# main.net
KiCad netlist of a schematic drawn in Altium Designer
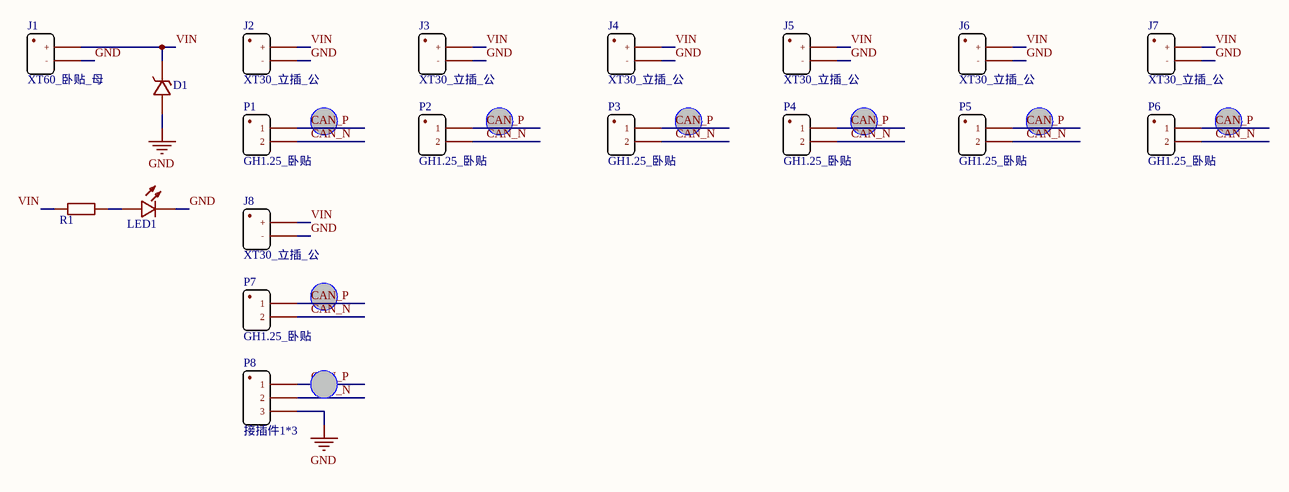
[diagram p0: main.SchDoc]

(export (version "E")
  (design (tool "Eeschema 10.0.6"))
  (components
    (comp (ref "D1") (value "SMAJ24A") (footprint "SMA") (libsource (lib "元件库") (part "二极管_瞬态抑制")))
    (comp (ref "J1") (value "XT60_卧贴_母") (footprint "XT60-PT-M") (libsource (lib "接口库") (part "接口_XT")))
    (comp (ref "J2") (value "XT30_立插_公") (footprint "XT30-UPB-F") (libsource (lib "接口库") (part "接口_XT")))
    (comp (ref "J3") (value "XT30_立插_公") (footprint "XT30-UPB-F") (libsource (lib "接口库") (part "接口_XT")))
    (comp (ref "J4") (value "XT30_立插_公") (footprint "XT30-UPB-F") (libsource (lib "接口库") (part "接口_XT")))
    (comp (ref "J5") (value "XT30_立插_公") (footprint "XT30-UPB-F") (libsource (lib "接口库") (part "接口_XT")))
    (comp (ref "J6") (value "XT30_立插_公") (footprint "XT30-UPB-F") (libsource (lib "接口库") (part "接口_XT")))
    (comp (ref "J7") (value "XT30_立插_公") (footprint "XT30-UPB-F") (libsource (lib "接口库") (part "接口_XT")))
    (comp (ref "J8") (value "XT30_立插_公") (footprint "XT30-UPB-F") (libsource (lib "接口库") (part "接口_XT")))
    (comp (ref "LED1") (value "LED") (footprint "0603D") (libsource (lib "元件库") (part "二极管_贴片发光")))
    (comp (ref "P1") (value "GH1.25_卧贴") (footprint "GH1.25-PW-1*2") (libsource (lib "接口库") (part "接插件1*2")))
    (comp (ref "P2") (value "GH1.25_卧贴") (footprint "GH1.25-PW-1*2") (libsource (lib "接口库") (part "接插件1*2")))
    (comp (ref "P3") (value "GH1.25_卧贴") (footprint "GH1.25-PW-1*2") (libsource (lib "接口库") (part "接插件1*2")))
    (comp (ref "P4") (value "GH1.25_卧贴") (footprint "GH1.25-PW-1*2") (libsource (lib "接口库") (part "接插件1*2")))
    (comp (ref "P5") (value "GH1.25_卧贴") (footprint "GH1.25-PW-1*2") (libsource (lib "接口库") (part "接插件1*2")))
    (comp (ref "P6") (value "GH1.25_卧贴") (footprint "GH1.25-PW-1*2") (libsource (lib "接口库") (part "接插件1*2")))
    (comp (ref "P7") (value "GH1.25_卧贴") (footprint "GH1.25-PW-1*2") (libsource (lib "接口库") (part "接插件1*2")))
    (comp (ref "P8") (value "接插件1*3") (footprint "GH1.25-PW-1*3") (libsource (lib "接口库") (part "接插件1*3")))
    (comp (ref "R1") (value "10K") (footprint "0603R") (libsource (lib "元件库") (part "电阻_贴片")))
  )
  (nets
    (net (code "1") (name "/CAN_N") (class "Default")
      (node (ref "P1") (pin "2") (pinfunction "2_2") (pintype "passive"))
      (node (ref "P2") (pin "2") (pinfunction "2_2") (pintype "passive"))
      (node (ref "P3") (pin "2") (pinfunction "2_2") (pintype "passive"))
      (node (ref "P4") (pin "2") (pinfunction "2_2") (pintype "passive"))
      (node (ref "P5") (pin "2") (pinfunction "2_2") (pintype "passive"))
      (node (ref "P6") (pin "2") (pinfunction "2_2") (pintype "passive"))
      (node (ref "P7") (pin "2") (pinfunction "2_2") (pintype "passive"))
      (node (ref "P8") (pin "2") (pinfunction "2_2") (pintype "passive"))
    )
    (net (code "2") (name "/CAN_P") (class "Default")
      (node (ref "P1") (pin "1") (pinfunction "1_1") (pintype "passive"))
      (node (ref "P2") (pin "1") (pinfunction "1_1") (pintype "passive"))
      (node (ref "P3") (pin "1") (pinfunction "1_1") (pintype "passive"))
      (node (ref "P4") (pin "1") (pinfunction "1_1") (pintype "passive"))
      (node (ref "P5") (pin "1") (pinfunction "1_1") (pintype "passive"))
      (node (ref "P6") (pin "1") (pinfunction "1_1") (pintype "passive"))
      (node (ref "P7") (pin "1") (pinfunction "1_1") (pintype "passive"))
      (node (ref "P8") (pin "1") (pinfunction "1_1") (pintype "passive"))
    )
    (net (code "3") (name "/VIN") (class "Default")
      (node (ref "D1") (pin "2") (pinfunction "2_2") (pintype "passive"))
      (node (ref "J1") (pin "1") (pinfunction "1_1") (pintype "passive"))
      (node (ref "J2") (pin "1") (pinfunction "1_1") (pintype "passive"))
      (node (ref "J3") (pin "1") (pinfunction "1_1") (pintype "passive"))
      (node (ref "J4") (pin "1") (pinfunction "1_1") (pintype "passive"))
      (node (ref "J5") (pin "1") (pinfunction "1_1") (pintype "passive"))
      (node (ref "J6") (pin "1") (pinfunction "1_1") (pintype "passive"))
      (node (ref "J7") (pin "1") (pinfunction "1_1") (pintype "passive"))
      (node (ref "J8") (pin "1") (pinfunction "1_1") (pintype "passive"))
      (node (ref "R1") (pin "1") (pinfunction "1_1") (pintype "passive"))
    )
    (net (code "4") (name "GND") (class "Default")
      (node (ref "D1") (pin "1") (pinfunction "1_1") (pintype "passive"))
      (node (ref "J1") (pin "2") (pinfunction "2_2") (pintype "passive"))
      (node (ref "J2") (pin "2") (pinfunction "2_2") (pintype "passive"))
      (node (ref "J3") (pin "2") (pinfunction "2_2") (pintype "passive"))
      (node (ref "J4") (pin "2") (pinfunction "2_2") (pintype "passive"))
      (node (ref "J5") (pin "2") (pinfunction "2_2") (pintype "passive"))
      (node (ref "J6") (pin "2") (pinfunction "2_2") (pintype "passive"))
      (node (ref "J7") (pin "2") (pinfunction "2_2") (pintype "passive"))
      (node (ref "J8") (pin "2") (pinfunction "2_2") (pintype "passive"))
      (node (ref "LED1") (pin "2") (pinfunction "2_2") (pintype "passive"))
      (node (ref "P8") (pin "3") (pinfunction "3_3") (pintype "passive"))
    )
    (net (code "5") (name "Net-(LED1-Pad1)") (class "Default")
      (node (ref "LED1") (pin "1") (pinfunction "1_1") (pintype "passive"))
      (node (ref "R1") (pin "2") (pinfunction "2_2") (pintype "passive"))
    )
  )
)
